# caphumidsens_rev1.net
KiCad netlist of a schematic drawn in EAGLE
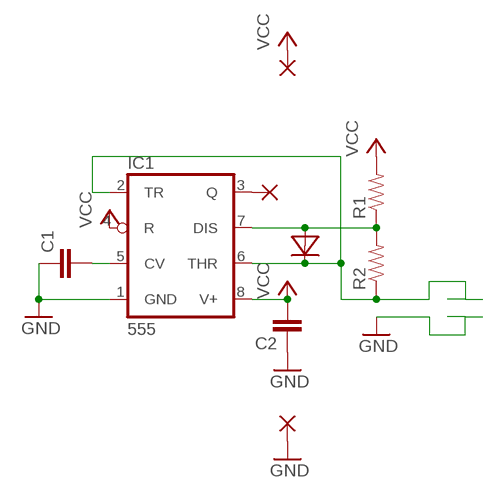
[diagram p0: schematic, sheet 1]

(export (version "E")
  (design (tool "Eeschema 10.0.6"))
  (components
    (comp (ref "C1")
      (value "CAP0805")
      (footprint "eagle-import:0805")
      (libsource (lib "eagle-import") (part "CAP0805"))
    )
    (comp (ref "C2")
      (value "CAP0805")
      (footprint "eagle-import:0805")
      (libsource (lib "eagle-import") (part "CAP0805"))
    )
    (comp (ref "D1")
      (value "DIODE_0805")
      (footprint "eagle-import:DIODE_0805")
      (libsource (lib "eagle-import") (part "DIODE_0805"))
    )
    (comp (ref "GND")
      (value "WIREPADSMD2,54-5,08")
      (footprint "eagle-import:SMD2,54-5,08")
      (libsource (lib "eagle-import") (part "WIREPADSMD2,54-5,08"))
    )
    (comp (ref "IC1")
      (value "555")
      (footprint "eagle-import:SO08")
      (libsource (lib "eagle-import") (part "555DNE"))
    )
    (comp (ref "OUT")
      (value "WIREPADSMD2,54-5,08")
      (footprint "eagle-import:SMD2,54-5,08")
      (libsource (lib "eagle-import") (part "WIREPADSMD2,54-5,08"))
    )
    (comp (ref "R1")
      (value "RESISTOR0805-RES")
      (footprint "eagle-import:0805")
      (libsource (lib "eagle-import") (part "RESISTOR0805-RES"))
    )
    (comp (ref "R2")
      (value "RESISTOR0805-RES")
      (footprint "eagle-import:0805")
      (libsource (lib "eagle-import") (part "RESISTOR0805-RES"))
    )
    (comp (ref "VCC")
      (value "WIREPADSMD2,54-5,08")
      (footprint "eagle-import:SMD2,54-5,08")
      (libsource (lib "eagle-import") (part "WIREPADSMD2,54-5,08"))
    )
  )
  (nets
    (net (code "1") (name "GND") (class "Default")
      (node (ref "C1") (pin "1") (pinfunction "1_1") (pintype "passive"))
      (node (ref "C2") (pin "1") (pinfunction "1_1") (pintype "passive"))
      (node (ref "GND") (pin "1") (pinfunction "P_1") (pintype "passive"))
      (node (ref "IC1") (pin "1") (pinfunction "GND_1") (pintype "power_in"))
    )
    (net (code "2") (name "Net-(D1-A)") (class "Default")
      (node (ref "D1") (pin "2") (pinfunction "A_2") (pintype "passive"))
      (node (ref "IC1") (pin "7") (pinfunction "DIS_7") (pintype "input"))
      (node (ref "R1") (pin "1") (pinfunction "1_1") (pintype "passive"))
      (node (ref "R2") (pin "2") (pinfunction "2_2") (pintype "passive"))
    )
    (net (code "3") (name "Net-(D1-C)") (class "Default")
      (node (ref "D1") (pin "1") (pinfunction "C_1") (pintype "passive"))
      (node (ref "IC1") (pin "2") (pinfunction "TR_2") (pintype "input"))
      (node (ref "IC1") (pin "6") (pinfunction "THR_6") (pintype "input"))
      (node (ref "R2") (pin "1") (pinfunction "1_1") (pintype "passive"))
    )
    (net (code "4") (name "Net-(IC1-CV)") (class "Default")
      (node (ref "C1") (pin "2") (pinfunction "2_2") (pintype "passive"))
      (node (ref "IC1") (pin "5") (pinfunction "CV_5") (pintype "input"))
    )
    (net (code "5") (name "Net-(IC1-Q)") (class "Default")
      (node (ref "IC1") (pin "3") (pinfunction "Q_3") (pintype "output"))
      (node (ref "OUT") (pin "1") (pinfunction "P_1") (pintype "passive"))
    )
    (net (code "6") (name "VCC") (class "Default")
      (node (ref "C2") (pin "2") (pinfunction "2_2") (pintype "passive"))
      (node (ref "IC1") (pin "4") (pinfunction "R_4") (pintype "input"))
      (node (ref "IC1") (pin "8") (pinfunction "V+_8") (pintype "power_in"))
      (node (ref "R1") (pin "2") (pinfunction "2_2") (pintype "passive"))
      (node (ref "VCC") (pin "1") (pinfunction "P_1") (pintype "passive"))
    )
  )
)
